# QCopterFly_POWER_Sch.net
KiCad netlist of a schematic drawn in Altium Designer
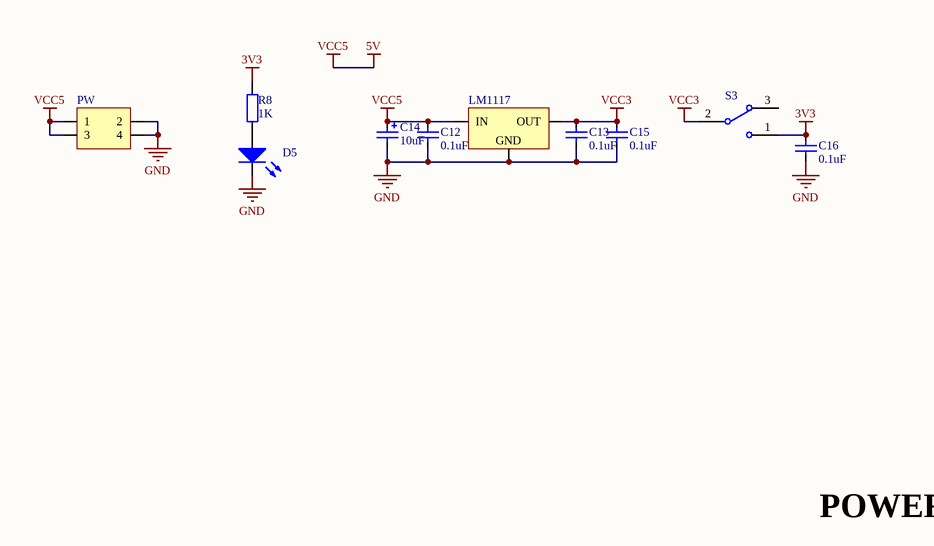
[diagram p0: QCopterFly_POWER_Sch.SchDoc]

(export (version "E")
  (design (tool "Eeschema 10.0.6"))
  (components
    (comp (ref "C12")
      (value "0.1uF")
      (footprint "PCB_Passive:CAP_0603")
      (description "Capacitor")
      (fields (field (name "Comment") "Cap_0603"))
      (libsource (lib "SCH_Passive") (part "Cap_0603"))
    )
    (comp (ref "C13")
      (value "0.1uF")
      (footprint "PCB_Passive:CAP_0603")
      (description "Capacitor")
      (fields (field (name "Comment") "Cap_0603"))
      (libsource (lib "SCH_Passive") (part "Cap_0603"))
    )
    (comp (ref "C14")
      (value "10uF")
      (footprint "PCB_Passive:CAP_TAN_B1210")
      (description "Capacitor")
      (fields (field (name "Comment") "Cap_Tan_1210"))
      (libsource (lib "SCH_Passive") (part "Cap_Tan_1210"))
    )
    (comp (ref "C15")
      (value "0.1uF")
      (footprint "PCB_Passive:CAP_0603")
      (description "Capacitor")
      (fields (field (name "Comment") "Cap_0603"))
      (libsource (lib "SCH_Passive") (part "Cap_0603"))
    )
    (comp (ref "C16")
      (value "0.1uF")
      (footprint "PCB_Passive:CAP_0603")
      (description "Capacitor")
      (fields (field (name "Comment") "Cap_0603"))
      (libsource (lib "SCH_Passive") (part "Cap_0603"))
    )
    (comp (ref "D5")
      (value "LED_0603_BLUE")
      (footprint "PCB_Active:LED_0603_BLUE")
      (description "LED")
      (libsource (lib "SCH_Active") (part "LED_0603_BLUE"))
    )
    (comp (ref "LM1")
      (value "LM1117")
      (footprint "PCB_IC:SOT223")
      (description "Power")
      (libsource (lib "SCH_IC") (part "LM1117"))
    )
    (comp (ref "PW")
      (value "HDR2X2_90_2.54")
      (footprint "PCB_Connector:HDR2X2_90_2.54")
      (description "Header")
      (libsource (lib "SCH_Connector") (part "HDR2X2_90_2.54"))
    )
    (comp (ref "R8")
      (value "1K")
      (footprint "PCB_Passive:RES_0603")
      (description "Resistor")
      (fields (field (name "Comment") "Res_0603"))
      (libsource (lib "SCH_Passive") (part "Res_0603"))
    )
    (comp (ref "S3")
      (value "SW-SPDT")
      (footprint "PCB_Switch:SW_T")
      (description "SPDT Subminiature Toggle Switch, Right Angle Mounting, Vertical Actuation")
      (fields (field (name "PUBLISHER") "Altium Limited"))
      (libsource (lib "SCH_Switch") (part "SW-SPDT_1"))
    )
  )
  (nets
    (net (code "1") (name "3V3") (class "Default")
      (node (ref "C16") (pin "2") (pinfunction "2_2") (pintype "passive"))
      (node (ref "R8") (pin "2") (pinfunction "2_2") (pintype "passive"))
      (node (ref "S3") (pin "1") (pinfunction "1_1") (pintype "passive"))
    )
    (net (code "2") (name "5V") (class "Default")
      (node (ref "C12") (pin "2") (pinfunction "2_2") (pintype "passive"))
      (node (ref "C14") (pin "1") (pinfunction "1_1") (pintype "passive"))
      (node (ref "LM1") (pin "3") (pinfunction "IN_3") (pintype "power_in"))
      (node (ref "PW") (pin "1") (pinfunction "1_1") (pintype "passive"))
      (node (ref "PW") (pin "3") (pinfunction "3_3") (pintype "passive"))
    )
    (net (code "3") (name "GND") (class "Default")
      (node (ref "C12") (pin "1") (pinfunction "1_1") (pintype "passive"))
      (node (ref "C13") (pin "1") (pinfunction "1_1") (pintype "passive"))
      (node (ref "C14") (pin "2") (pinfunction "2_2") (pintype "passive"))
      (node (ref "C15") (pin "1") (pinfunction "1_1") (pintype "passive"))
      (node (ref "C16") (pin "1") (pinfunction "1_1") (pintype "passive"))
      (node (ref "D5") (pin "2") (pinfunction "K_2") (pintype "passive"))
      (node (ref "LM1") (pin "1") (pinfunction "GND_1") (pintype "power_in"))
      (node (ref "PW") (pin "2") (pinfunction "2_2") (pintype "passive"))
      (node (ref "PW") (pin "4") (pinfunction "4_4") (pintype "passive"))
    )
    (net (code "4") (name "Net-(D5-A)") (class "Default")
      (node (ref "D5") (pin "1") (pinfunction "A_1") (pintype "passive"))
      (node (ref "R8") (pin "1") (pinfunction "1_1") (pintype "passive"))
    )
    (net (code "5") (name "VCC3") (class "Default")
      (node (ref "C13") (pin "2") (pinfunction "2_2") (pintype "passive"))
      (node (ref "C15") (pin "2") (pinfunction "2_2") (pintype "passive"))
      (node (ref "LM1") (pin "2") (pinfunction "OUT_2") (pintype "power_in"))
      (node (ref "S3") (pin "2") (pinfunction "2_2") (pintype "passive"))
    )
    (net (code "6") (name "unconnected-(S3-Pad3)") (class "Default")
      (node (ref "S3") (pin "3") (pinfunction "3_3") (pintype "passive"))
    )
  )
)
